# board.net
KiCad netlist of a schematic drawn in EAGLE
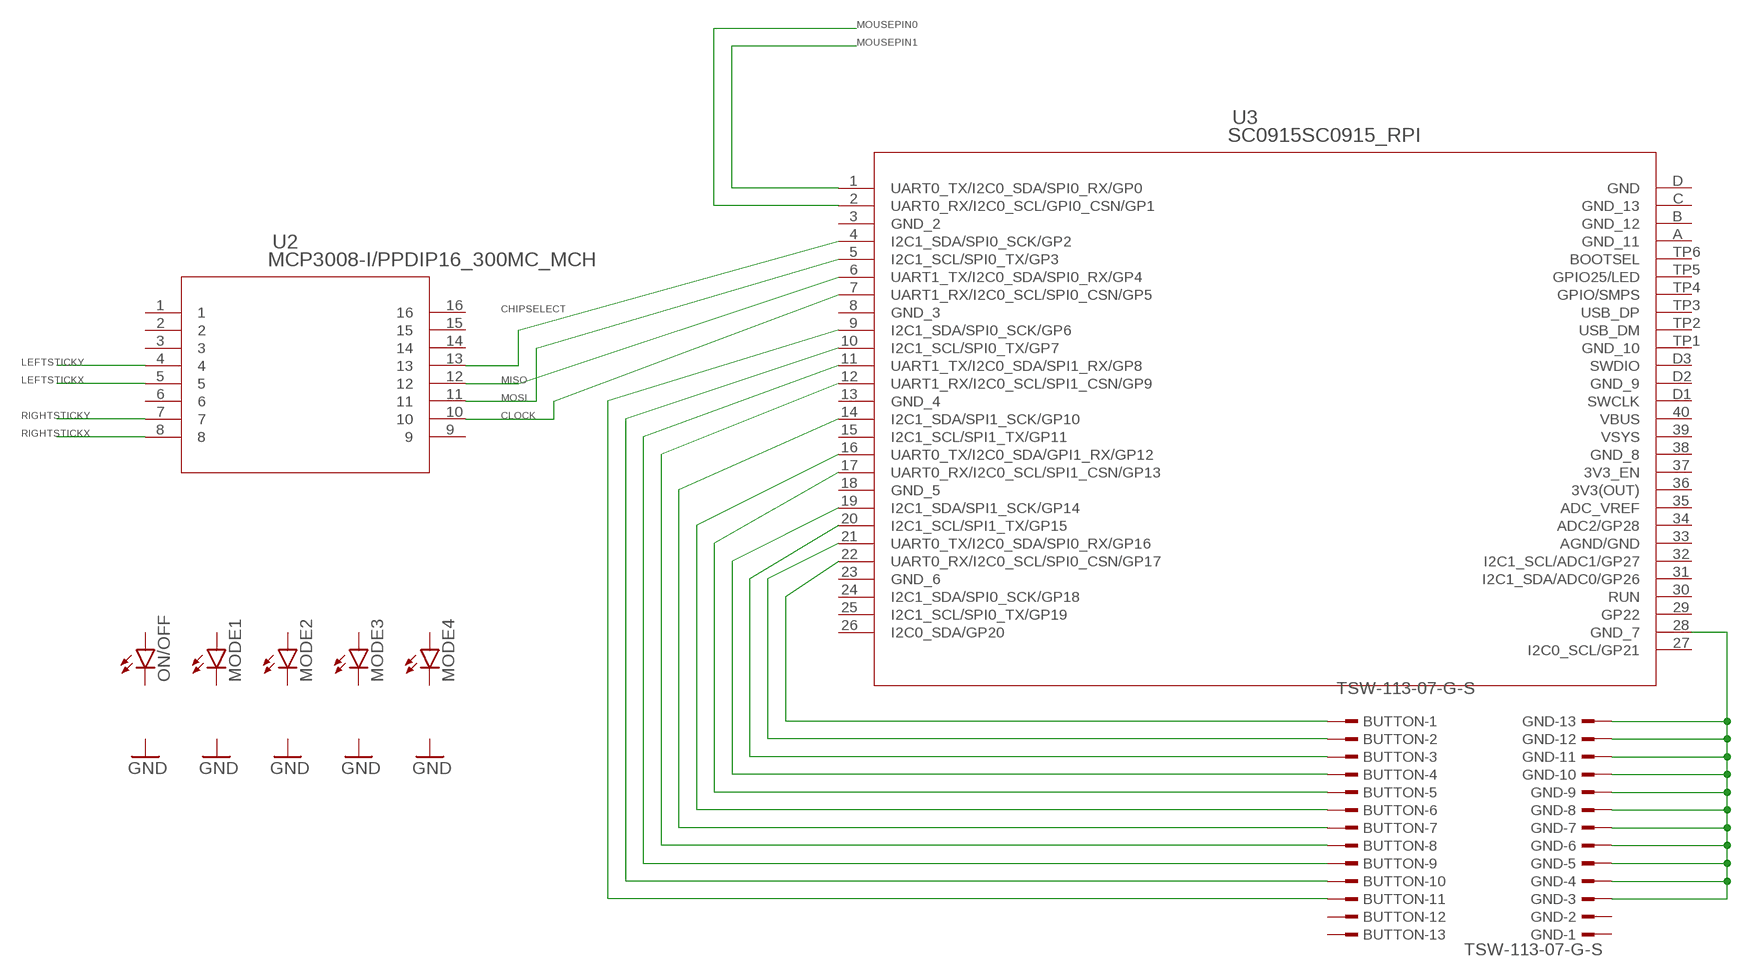
[diagram p0: schematic, sheet 1]

(export (version "E")
  (design (tool "Eeschema 10.0.6"))
  (components
    (comp (ref "BUTTON")
      (value "TSW-113-07-G-S")
      (footprint "eagle-import:TSW-113-XX-G-S")
      (fields (field (name "MF") "Samtec Inc."))
      (libsource (lib "eagle-import") (part "TSW-113--G-S07"))
    )
    (comp (ref "GND")
      (value "TSW-113-07-G-S")
      (footprint "eagle-import:TSW-113-XX-G-S")
      (fields (field (name "MF") "Samtec Inc."))
      (libsource (lib "eagle-import") (part "TSW-113--G-S07"))
    )
    (comp (ref "MODE1")
      (value "LED5MM")
      (footprint "eagle-import:LED5MM")
      (libsource (lib "eagle-import") (part "LED5MM"))
    )
    (comp (ref "MODE2")
      (value "LED5MM")
      (footprint "eagle-import:LED5MM")
      (libsource (lib "eagle-import") (part "LED5MM"))
    )
    (comp (ref "MODE3")
      (value "LED5MM")
      (footprint "eagle-import:LED5MM")
      (libsource (lib "eagle-import") (part "LED5MM"))
    )
    (comp (ref "MODE4")
      (value "LED5MM")
      (footprint "eagle-import:LED5MM")
      (libsource (lib "eagle-import") (part "LED5MM"))
    )
    (comp (ref "ON/OFF")
      (value "LED5MM")
      (footprint "eagle-import:LED5MM")
      (libsource (lib "eagle-import") (part "LED5MM"))
    )
    (comp (ref "U2")
      (value "MCP3008-I/PPDIP16_300MC_MCH")
      (footprint "eagle-import:PDIP16_300MC_MCH")
      (fields
        (field (name "MANUFACTURER_PART_NUMBER") "MCP3008-I/P")
        (field (name "COPYRIGHT") "Copyright (C) 2022 Ultra Librarian. All rights reserved.")
      )
      (libsource (lib "eagle-import") (part "MCP3008-I/PPDIP16_300MC_MCH"))
    )
    (comp (ref "U3")
      (value "SC0915SC0915_RPI")
      (footprint "eagle-import:SC0915_RPI")
      (fields
        (field (name "MANUFACTURER_PART_NUMBER") "SC0915")
        (field (name "COPYRIGHT") "Copyright (C) 2022 Ultra Librarian. All rights reserved.")
      )
      (libsource (lib "eagle-import") (part "SC0915SC0915_RPI"))
    )
  )
  (nets
    (net (code "1") (name "/3V3_EN") (class "Default")
      (node (ref "U3") (pin "37") (pinfunction "3V3_EN_37") (pintype "power_in"))
    )
    (net (code "2") (name "/ADC_VREF") (class "Default")
      (node (ref "U3") (pin "35") (pinfunction "ADC_VREF_35") (pintype "power_in"))
    )
    (net (code "3") (name "/CHIPSELECT") (class "Default")
      (node (ref "U2") (pin "13") (pinfunction "13_13") (pintype "passive"))
      (node (ref "U3") (pin "4") (pinfunction "I2C1_SDA/SPI0_SCK/GP2_4") (pintype "bidirectional"))
    )
    (net (code "4") (name "/CLOCK") (class "Default")
      (node (ref "U2") (pin "10") (pinfunction "10_10") (pintype "passive"))
      (node (ref "U3") (pin "7") (pinfunction "UART1_RX/I2C0_SCL/SPI0_CSN/GP5_7") (pintype "bidirectional"))
    )
    (net (code "5") (name "/LEFTSTICKX") (class "Default")
      (node (ref "U2") (pin "5") (pinfunction "5_5") (pintype "passive"))
    )
    (net (code "6") (name "/LEFTSTICKY") (class "Default")
      (node (ref "U2") (pin "4") (pinfunction "4_4") (pintype "passive"))
    )
    (net (code "7") (name "/MISO") (class "Default")
      (node (ref "U2") (pin "12") (pinfunction "12_12") (pintype "passive"))
      (node (ref "U3") (pin "6") (pinfunction "UART1_TX/I2C0_SDA/SPI0_RX/GP4_6") (pintype "bidirectional"))
    )
    (net (code "8") (name "/MOSI") (class "Default")
      (node (ref "U2") (pin "11") (pinfunction "11_11") (pintype "passive"))
      (node (ref "U3") (pin "5") (pinfunction "I2C1_SCL/SPI0_TX/GP3_5") (pintype "bidirectional"))
    )
    (net (code "9") (name "/MOUSEPIN0") (class "Default")
      (node (ref "U3") (pin "2") (pinfunction "UART0_RX/I2C0_SCL/GPI0_CSN/GP1_2") (pintype "bidirectional"))
    )
    (net (code "10") (name "/MOUSEPIN1") (class "Default")
      (node (ref "U3") (pin "1") (pinfunction "UART0_TX/I2C0_SDA/SPI0_RX/GP0_1") (pintype "bidirectional"))
    )
    (net (code "11") (name "/RIGHTSTICKX") (class "Default")
      (node (ref "U2") (pin "8") (pinfunction "8_8") (pintype "passive"))
    )
    (net (code "12") (name "/RIGHTSTICKY") (class "Default")
      (node (ref "U2") (pin "7") (pinfunction "7_7") (pintype "passive"))
    )
    (net (code "13") (name "/VBUS") (class "Default")
      (node (ref "U3") (pin "40") (pinfunction "VBUS_40") (pintype "power_in"))
    )
    (net (code "14") (name "/VSYS") (class "Default")
      (node (ref "U3") (pin "39") (pinfunction "VSYS_39") (pintype "power_in"))
    )
    (net (code "16") (name "Net-(BUTTONB-1)") (class "Default")
      (node (ref "BUTTON") (pin "10") (pinfunction "1_10") (pintype "passive"))
      (node (ref "U3") (pin "10") (pinfunction "I2C1_SCL/SPI0_TX/GP7_10") (pintype "bidirectional"))
    )
    (net (code "17") (name "Net-(BUTTONC-1)") (class "Default")
      (node (ref "BUTTON") (pin "11") (pinfunction "1_11") (pintype "passive"))
      (node (ref "U3") (pin "9") (pinfunction "I2C1_SDA/SPI0_SCK/GP6_9") (pintype "bidirectional"))
    )
    (net (code "18") (name "Net-(BUTTONF-1)") (class "Default")
      (node (ref "BUTTON") (pin "2") (pinfunction "1_2") (pintype "passive"))
      (node (ref "U3") (pin "21") (pinfunction "UART0_TX/I2C0_SDA/SPI0_RX/GP16_21") (pintype "bidirectional"))
    )
    (net (code "19") (name "Net-(BUTTONG-1)") (class "Default")
      (node (ref "BUTTON") (pin "3") (pinfunction "1_3") (pintype "passive"))
      (node (ref "U3") (pin "20") (pinfunction "I2C1_SCL/SPI1_TX/GP15_20") (pintype "bidirectional"))
    )
    (net (code "20") (name "Net-(BUTTONH-1)") (class "Default")
      (node (ref "BUTTON") (pin "4") (pinfunction "1_4") (pintype "passive"))
      (node (ref "U3") (pin "19") (pinfunction "I2C1_SDA/SPI1_SCK/GP14_19") (pintype "bidirectional"))
    )
    (net (code "21") (name "Net-(BUTTONI-1)") (class "Default")
      (node (ref "BUTTON") (pin "5") (pinfunction "1_5") (pintype "passive"))
      (node (ref "U3") (pin "17") (pinfunction "UART0_RX/I2C0_SCL/SPI1_CSN/GP13_17") (pintype "bidirectional"))
    )
    (net (code "22") (name "Net-(BUTTONJ-1)") (class "Default")
      (node (ref "BUTTON") (pin "6") (pinfunction "1_6") (pintype "passive"))
      (node (ref "U3") (pin "16") (pinfunction "UART0_TX/I2C0_SDA/GPI1_RX/GP12_16") (pintype "bidirectional"))
    )
    (net (code "23") (name "Net-(BUTTONK-1)") (class "Default")
      (node (ref "BUTTON") (pin "7") (pinfunction "1_7") (pintype "passive"))
      (node (ref "U3") (pin "14") (pinfunction "I2C1_SDA/SPI1_SCK/GP10_14") (pintype "bidirectional"))
    )
    (net (code "24") (name "Net-(BUTTONL-1)") (class "Default")
      (node (ref "BUTTON") (pin "8") (pinfunction "1_8") (pintype "passive"))
      (node (ref "U3") (pin "12") (pinfunction "UART1_RX/I2C0_SCL/SPI1_CSN/GP9_12") (pintype "bidirectional"))
    )
    (net (code "25") (name "Net-(BUTTONM-1)") (class "Default")
      (node (ref "BUTTON") (pin "9") (pinfunction "1_9") (pintype "passive"))
      (node (ref "U3") (pin "11") (pinfunction "UART1_TX/I2C0_SDA/SPI1_RX/GP8_11") (pintype "bidirectional"))
    )
    (net (code "26") (name "Net-(GNDB-1)") (class "Default")
      (node (ref "GND") (pin "10") (pinfunction "1_10") (pintype "passive"))
      (node (ref "GND") (pin "11") (pinfunction "1_11") (pintype "passive"))
      (node (ref "GND") (pin "12") (pinfunction "1_12") (pintype "passive"))
      (node (ref "GND") (pin "13") (pinfunction "1_13") (pintype "passive"))
      (node (ref "GND") (pin "3") (pinfunction "1_3") (pintype "passive"))
      (node (ref "GND") (pin "4") (pinfunction "1_4") (pintype "passive"))
      (node (ref "GND") (pin "5") (pinfunction "1_5") (pintype "passive"))
      (node (ref "GND") (pin "6") (pinfunction "1_6") (pintype "passive"))
      (node (ref "GND") (pin "7") (pinfunction "1_7") (pintype "passive"))
      (node (ref "GND") (pin "8") (pinfunction "1_8") (pintype "passive"))
      (node (ref "GND") (pin "9") (pinfunction "1_9") (pintype "passive"))
      (node (ref "U3") (pin "28") (pinfunction "GND_7_28") (pintype "passive"))
    )
    (net (code "27") (name "Net-(U3-UART0_RX{slash}I2C0_SCL{slash}SPI0_CSN{slash}GP17)") (class "Default")
      (node (ref "BUTTON") (pin "1") (pinfunction "1_1") (pintype "passive"))
      (node (ref "U3") (pin "22") (pinfunction "UART0_RX/I2C0_SCL/SPI0_CSN/GP17_22") (pintype "bidirectional"))
    )
    (net (code "28") (name "unconnected-(BUTTOND-1-Pad12)") (class "Default")
      (node (ref "BUTTON") (pin "12") (pinfunction "1_12") (pintype "passive"))
    )
    (net (code "29") (name "unconnected-(BUTTONE-1-Pad13)") (class "Default")
      (node (ref "BUTTON") (pin "13") (pinfunction "1_13") (pintype "passive"))
    )
    (net (code "30") (name "unconnected-(GND-Pad1)") (class "Default")
      (node (ref "GND") (pin "1") (pinfunction "1_1") (pintype "passive"))
    )
    (net (code "31") (name "unconnected-(GNDF-1-Pad2)") (class "Default")
      (node (ref "GND") (pin "2") (pinfunction "1_2") (pintype "passive"))
    )
    (net (code "32") (name "unconnected-(MODE1-C-PadK)") (class "Default")
      (node (ref "MODE1") (pin "K") (pinfunction "C_K") (pintype "passive"))
    )
    (net (code "33") (name "unconnected-(MODE1-PadA)") (class "Default")
      (node (ref "MODE1") (pin "A") (pinfunction "A_A") (pintype "passive"))
    )
    (net (code "34") (name "unconnected-(MODE2-C-PadK)") (class "Default")
      (node (ref "MODE2") (pin "K") (pinfunction "C_K") (pintype "passive"))
    )
    (net (code "35") (name "unconnected-(MODE2-PadA)") (class "Default")
      (node (ref "MODE2") (pin "A") (pinfunction "A_A") (pintype "passive"))
    )
    (net (code "36") (name "unconnected-(MODE3-C-PadK)") (class "Default")
      (node (ref "MODE3") (pin "K") (pinfunction "C_K") (pintype "passive"))
    )
    (net (code "37") (name "unconnected-(MODE3-PadA)") (class "Default")
      (node (ref "MODE3") (pin "A") (pinfunction "A_A") (pintype "passive"))
    )
    (net (code "38") (name "unconnected-(MODE4-C-PadK)") (class "Default")
      (node (ref "MODE4") (pin "K") (pinfunction "C_K") (pintype "passive"))
    )
    (net (code "39") (name "unconnected-(MODE4-PadA)") (class "Default")
      (node (ref "MODE4") (pin "A") (pinfunction "A_A") (pintype "passive"))
    )
    (net (code "40") (name "unconnected-(ON/OFF-C-PadK)") (class "Default")
      (node (ref "ON/OFF") (pin "K") (pinfunction "C_K") (pintype "passive"))
    )
    (net (code "41") (name "unconnected-(ON/OFF-PadA)") (class "Default")
      (node (ref "ON/OFF") (pin "A") (pinfunction "A_A") (pintype "passive"))
    )
    (net (code "42") (name "unconnected-(U2-Pad1)") (class "Default")
      (node (ref "U2") (pin "1") (pinfunction "1_1") (pintype "passive"))
    )
    (net (code "43") (name "unconnected-(U2-Pad2)") (class "Default")
      (node (ref "U2") (pin "2") (pinfunction "2_2") (pintype "passive"))
    )
    (net (code "44") (name "unconnected-(U2-Pad3)") (class "Default")
      (node (ref "U2") (pin "3") (pinfunction "3_3") (pintype "passive"))
    )
    (net (code "45") (name "unconnected-(U2-Pad6)") (class "Default")
      (node (ref "U2") (pin "6") (pinfunction "6_6") (pintype "passive"))
    )
    (net (code "46") (name "unconnected-(U2-Pad9)") (class "Default")
      (node (ref "U2") (pin "9") (pinfunction "9_9") (pintype "passive"))
    )
    (net (code "47") (name "unconnected-(U2-Pad14)") (class "Default")
      (node (ref "U2") (pin "14") (pinfunction "14_14") (pintype "passive"))
    )
    (net (code "48") (name "unconnected-(U2-Pad15)") (class "Default")
      (node (ref "U2") (pin "15") (pinfunction "15_15") (pintype "passive"))
    )
    (net (code "49") (name "unconnected-(U2-Pad16)") (class "Default")
      (node (ref "U2") (pin "16") (pinfunction "16_16") (pintype "passive"))
    )
    (net (code "50") (name "unconnected-(U3-3V3(OUT)-Pad36)") (class "Default")
      (node (ref "U3") (pin "36") (pinfunction "3V3(OUT)_36") (pintype "output"))
    )
    (net (code "51") (name "unconnected-(U3-ADC2{slash}GP28-Pad34)") (class "Default")
      (node (ref "U3") (pin "34") (pinfunction "ADC2/GP28_34") (pintype "bidirectional"))
    )
    (net (code "52") (name "unconnected-(U3-AGND{slash}GND-Pad33)") (class "Default")
      (node (ref "U3") (pin "33") (pinfunction "AGND/GND_33") (pintype "passive"))
    )
    (net (code "53") (name "unconnected-(U3-BOOTSEL-PadTP6)") (class "Default")
      (node (ref "U3") (pin "TP6") (pinfunction "BOOTSEL_TP6") (pintype "passive"))
    )
    (net (code "54") (name "unconnected-(U3-GND-PadD)") (class "Default")
      (node (ref "U3") (pin "D") (pinfunction "GND_D") (pintype "passive"))
    )
    (net (code "55") (name "unconnected-(U3-GND_2-Pad3)") (class "Default")
      (node (ref "U3") (pin "3") (pinfunction "GND_2_3") (pintype "passive"))
    )
    (net (code "56") (name "unconnected-(U3-GND_3-Pad8)") (class "Default")
      (node (ref "U3") (pin "8") (pinfunction "GND_3_8") (pintype "passive"))
    )
    (net (code "57") (name "unconnected-(U3-GND_4-Pad13)") (class "Default")
      (node (ref "U3") (pin "13") (pinfunction "GND_4_13") (pintype "passive"))
    )
    (net (code "58") (name "unconnected-(U3-GND_5-Pad18)") (class "Default")
      (node (ref "U3") (pin "18") (pinfunction "GND_5_18") (pintype "passive"))
    )
    (net (code "59") (name "unconnected-(U3-GND_6-Pad23)") (class "Default")
      (node (ref "U3") (pin "23") (pinfunction "GND_6_23") (pintype "passive"))
    )
    (net (code "60") (name "unconnected-(U3-GND_8-Pad38)") (class "Default")
      (node (ref "U3") (pin "38") (pinfunction "GND_8_38") (pintype "passive"))
    )
    (net (code "61") (name "unconnected-(U3-GND_9-PadD2)") (class "Default")
      (node (ref "U3") (pin "D2") (pinfunction "GND_9_D2") (pintype "passive"))
    )
    (net (code "62") (name "unconnected-(U3-GND_10-PadTP1)") (class "Default")
      (node (ref "U3") (pin "TP1") (pinfunction "GND_10_TP1") (pintype "passive"))
    )
    (net (code "63") (name "unconnected-(U3-GND_11-PadA)") (class "Default")
      (node (ref "U3") (pin "A") (pinfunction "GND_11_A") (pintype "passive"))
    )
    (net (code "64") (name "unconnected-(U3-GND_12-PadB)") (class "Default")
      (node (ref "U3") (pin "B") (pinfunction "GND_12_B") (pintype "passive"))
    )
    (net (code "65") (name "unconnected-(U3-GND_13-PadC)") (class "Default")
      (node (ref "U3") (pin "C") (pinfunction "GND_13_C") (pintype "passive"))
    )
    (net (code "66") (name "unconnected-(U3-GP22-Pad29)") (class "Default")
      (node (ref "U3") (pin "29") (pinfunction "GP22_29") (pintype "bidirectional"))
    )
    (net (code "67") (name "unconnected-(U3-GPIO25{slash}LED-PadTP5)") (class "Default")
      (node (ref "U3") (pin "TP5") (pinfunction "GPIO25/LED_TP5") (pintype "passive"))
    )
    (net (code "68") (name "unconnected-(U3-GPIO{slash}SMPS-PadTP4)") (class "Default")
      (node (ref "U3") (pin "TP4") (pinfunction "GPIO/SMPS_TP4") (pintype "passive"))
    )
    (net (code "69") (name "unconnected-(U3-I2C0_SCL{slash}GP21-Pad27)") (class "Default")
      (node (ref "U3") (pin "27") (pinfunction "I2C0_SCL/GP21_27") (pintype "bidirectional"))
    )
    (net (code "70") (name "unconnected-(U3-I2C0_SDA{slash}GP20-Pad26)") (class "Default")
      (node (ref "U3") (pin "26") (pinfunction "I2C0_SDA/GP20_26") (pintype "bidirectional"))
    )
    (net (code "71") (name "unconnected-(U3-I2C1_SCL{slash}ADC1{slash}GP27-Pad32)") (class "Default")
      (node (ref "U3") (pin "32") (pinfunction "I2C1_SCL/ADC1/GP27_32") (pintype "bidirectional"))
    )
    (net (code "72") (name "unconnected-(U3-I2C1_SCL{slash}SPI0_TX{slash}GP19-Pad25)") (class "Default")
      (node (ref "U3") (pin "25") (pinfunction "I2C1_SCL/SPI0_TX/GP19_25") (pintype "bidirectional"))
    )
    (net (code "73") (name "unconnected-(U3-I2C1_SCL{slash}SPI1_TX{slash}GP11-Pad15)") (class "Default")
      (node (ref "U3") (pin "15") (pinfunction "I2C1_SCL/SPI1_TX/GP11_15") (pintype "bidirectional"))
    )
    (net (code "74") (name "unconnected-(U3-I2C1_SDA{slash}ADC0{slash}GP26-Pad31)") (class "Default")
      (node (ref "U3") (pin "31") (pinfunction "I2C1_SDA/ADC0/GP26_31") (pintype "bidirectional"))
    )
    (net (code "75") (name "unconnected-(U3-I2C1_SDA{slash}SPI0_SCK{slash}GP18-Pad24)") (class "Default")
      (node (ref "U3") (pin "24") (pinfunction "I2C1_SDA/SPI0_SCK/GP18_24") (pintype "bidirectional"))
    )
    (net (code "76") (name "unconnected-(U3-RUN-Pad30)") (class "Default")
      (node (ref "U3") (pin "30") (pinfunction "RUN_30") (pintype "passive"))
    )
    (net (code "77") (name "unconnected-(U3-SWCLK-PadD1)") (class "Default")
      (node (ref "U3") (pin "D1") (pinfunction "SWCLK_D1") (pintype "passive"))
    )
    (net (code "78") (name "unconnected-(U3-SWDIO-PadD3)") (class "Default")
      (node (ref "U3") (pin "D3") (pinfunction "SWDIO_D3") (pintype "passive"))
    )
    (net (code "79") (name "unconnected-(U3-USB_DM-PadTP2)") (class "Default")
      (node (ref "U3") (pin "TP2") (pinfunction "USB_DM_TP2") (pintype "passive"))
    )
    (net (code "80") (name "unconnected-(U3-USB_DP-PadTP3)") (class "Default")
      (node (ref "U3") (pin "TP3") (pinfunction "USB_DP_TP3") (pintype "passive"))
    )
  )
)
